# MCB-EMW3166-v2_0_0.net
KiCad netlist of a schematic drawn in EAGLE
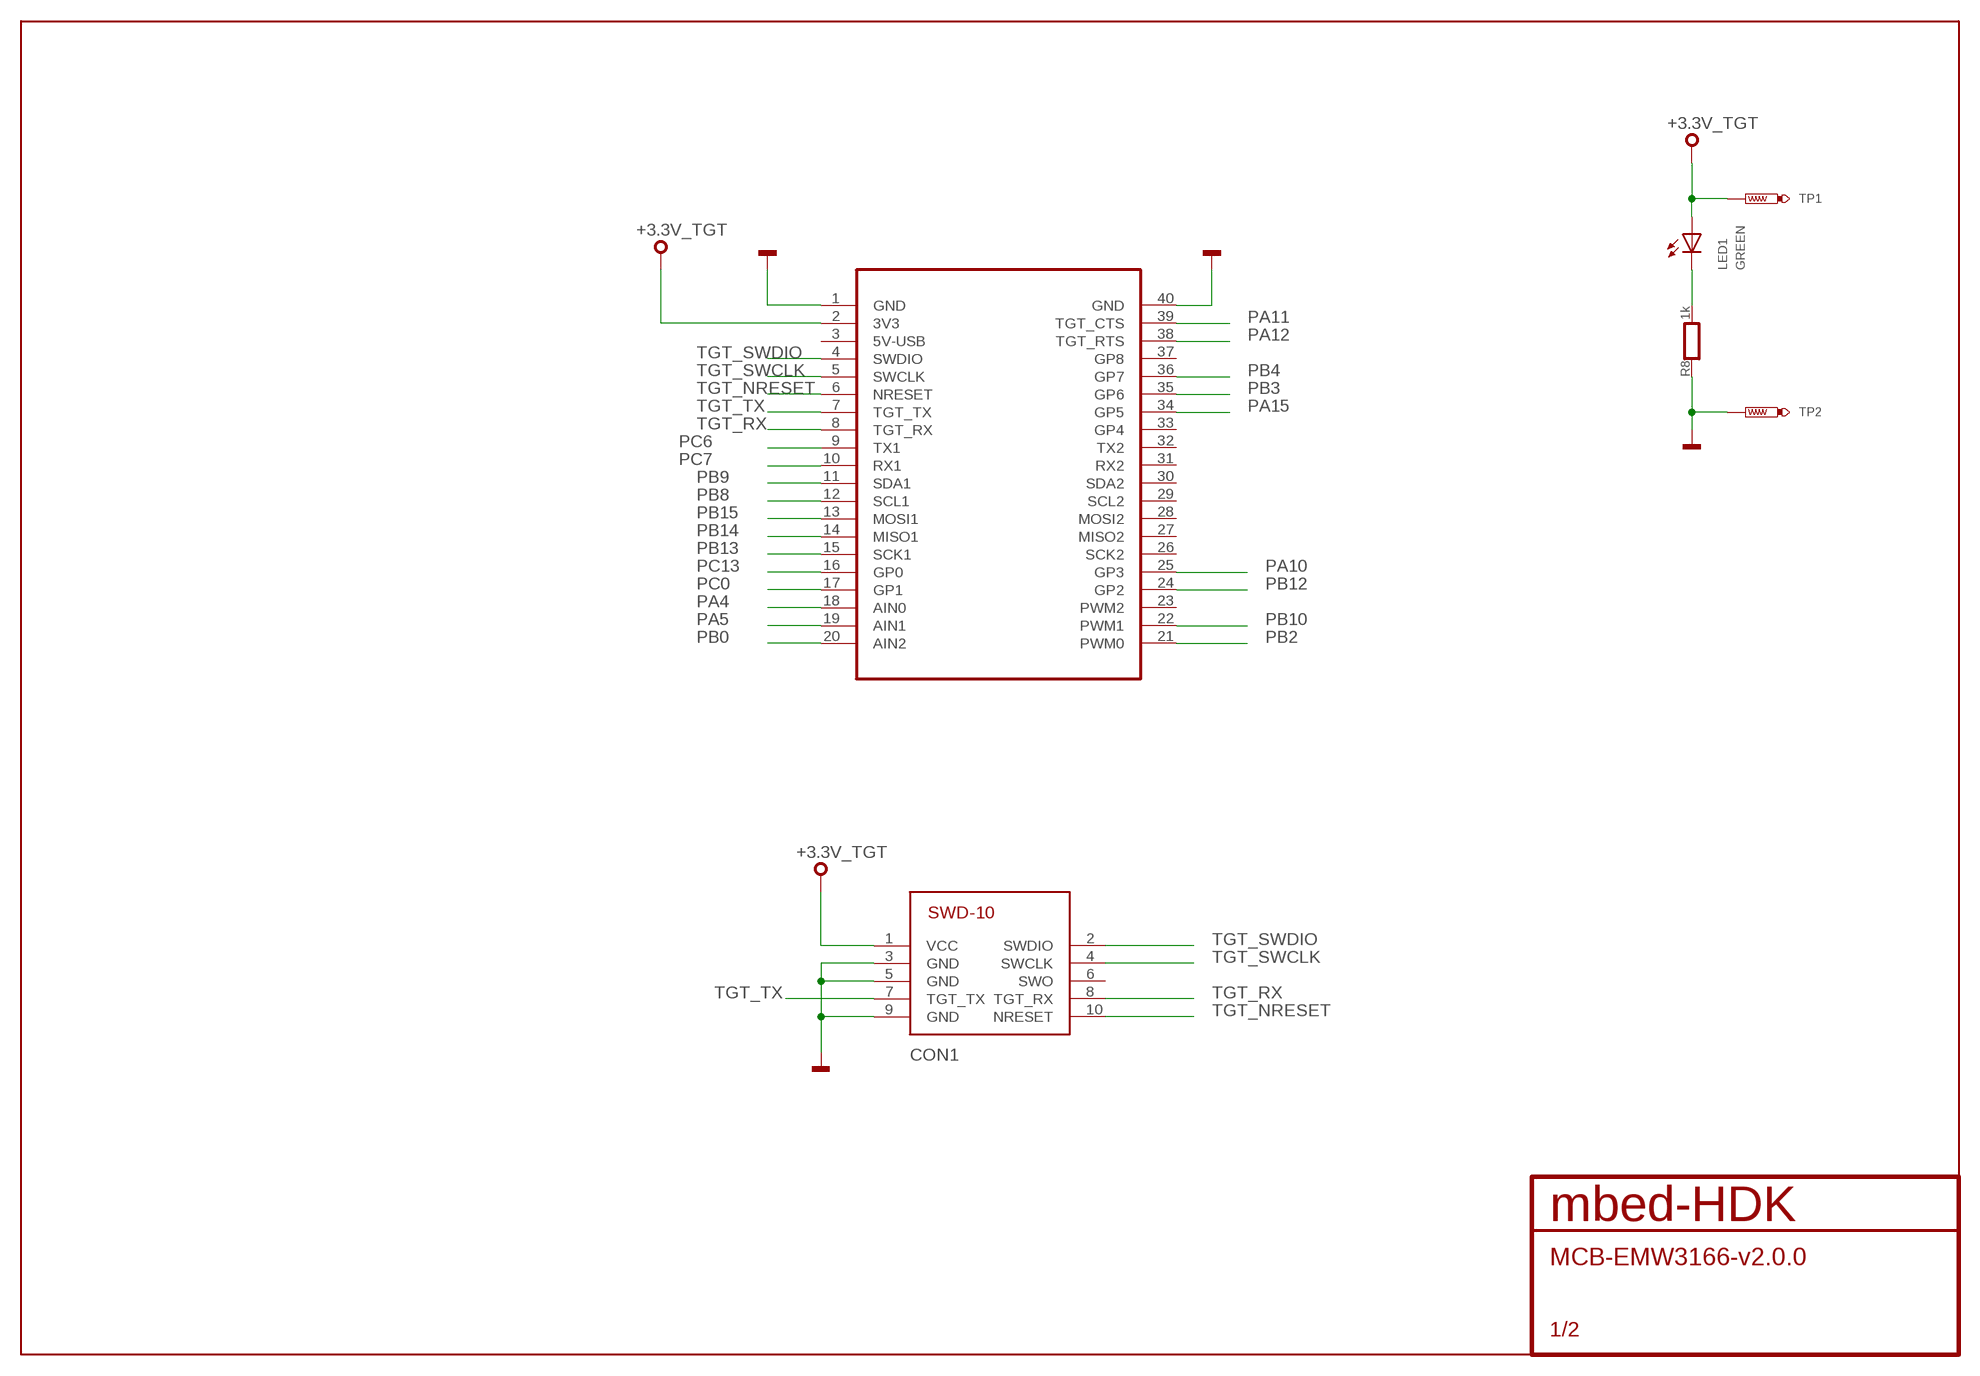
[diagram p0: schematic, sheet 1]
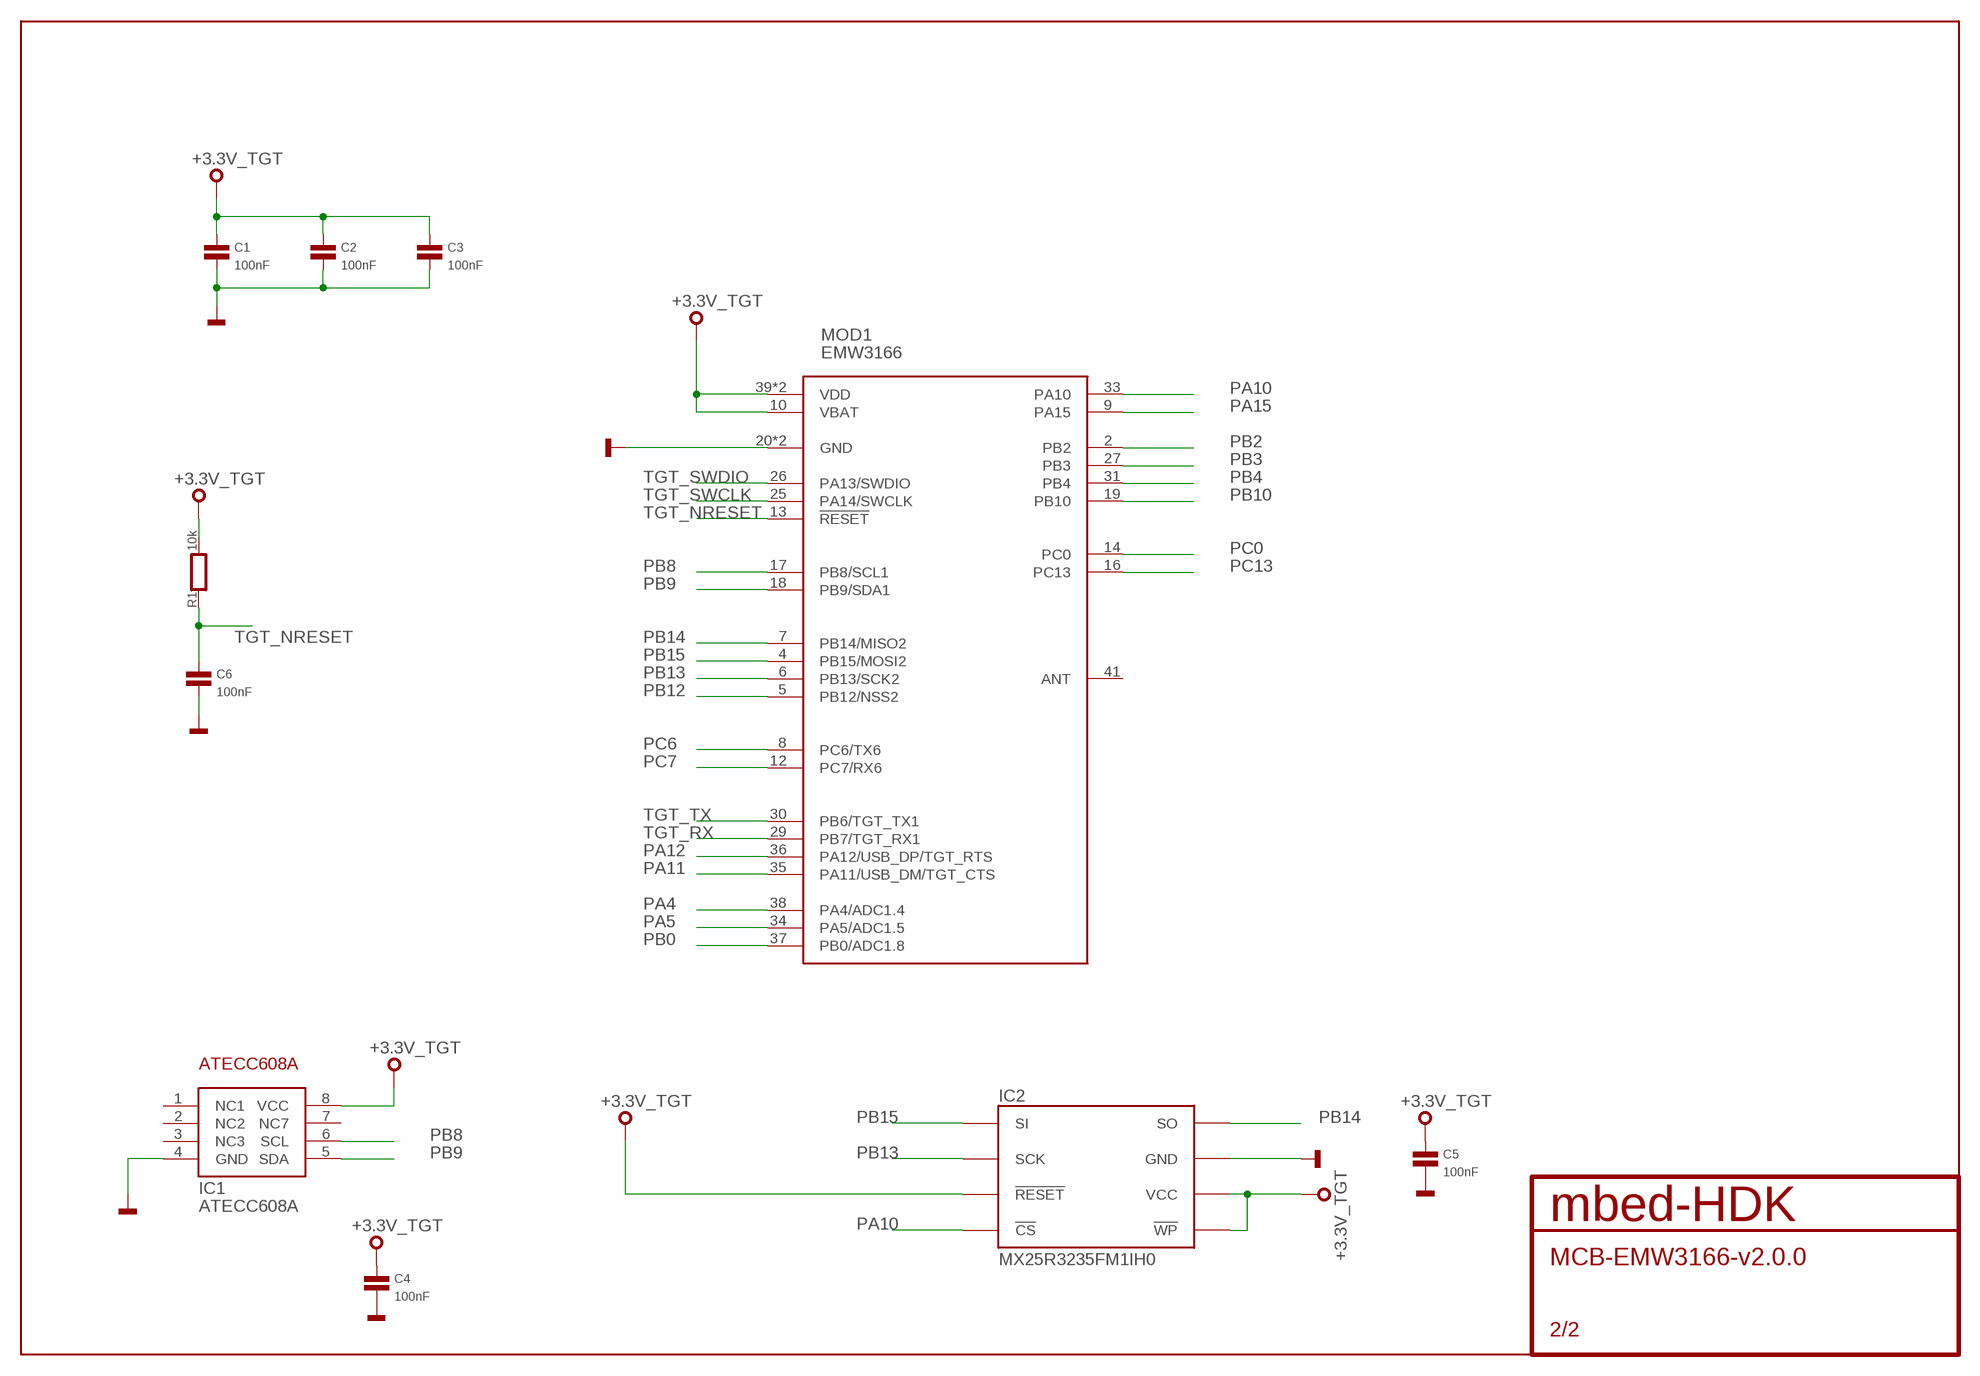
[diagram p1: schematic, sheet 2]

(export (version "E")
  (design (tool "Eeschema 10.0.6"))
  (components
    (comp (ref "C1")
      (value "100nF")
      (footprint "eagle-import:0603")
      (libsource (lib "eagle-import") (part "CAPACITOR0603"))
    )
    (comp (ref "C2")
      (value "100nF")
      (footprint "eagle-import:0603")
      (libsource (lib "eagle-import") (part "CAPACITOR0603"))
    )
    (comp (ref "C3")
      (value "100nF")
      (footprint "eagle-import:0603")
      (libsource (lib "eagle-import") (part "CAPACITOR0603"))
    )
    (comp (ref "C4")
      (value "100nF")
      (footprint "eagle-import:0603")
      (libsource (lib "eagle-import") (part "CAPACITOR0603"))
    )
    (comp (ref "C5")
      (value "100nF")
      (footprint "eagle-import:0603")
      (libsource (lib "eagle-import") (part "CAPACITOR0603"))
    )
    (comp (ref "C6")
      (value "100nF")
      (footprint "eagle-import:0603")
      (libsource (lib "eagle-import") (part "CAPACITOR0603"))
    )
    (comp (ref "IC1")
      (value "ATECC608A")
      (footprint "eagle-import:SO8")
      (libsource (lib "eagle-import") (part "ATECC608A"))
    )
    (comp (ref "IC2")
      (value "MX25R3235FM1IH0")
      (footprint "eagle-import:SO8")
      (fields (field (name "MF") "Macronix"))
      (libsource (lib "eagle-import") (part "MX25R3235FM1IH0"))
    )
    (comp (ref "MOD1")
      (value "EMW3166")
      (footprint "eagle-import:EMW3166")
      (libsource (lib "eagle-import") (part "EMW3166"))
    )
    (comp (ref "R1")
      (value "10k")
      (footprint "eagle-import:0603")
      (libsource (lib "eagle-import") (part "RESISTOR0603"))
    )
    (comp (ref "CON1")
      (value "SWD-10/TC2050_SMD")
      (footprint "eagle-import:FTSH-105-02")
      (libsource (lib "eagle-import") (part "SWD-10/TC2050_SMD"))
    )
    (comp (ref "LED1")
      (value "GREEN")
      (footprint "eagle-import:CHIPLED_0603")
      (fields (field (name "MF") "Wurth Electronics Inc"))
      (libsource (lib "eagle-import") (part "SMD_LED0603"))
    )
    (comp (ref "R8")
      (value "1k")
      (footprint "eagle-import:0603")
      (libsource (lib "eagle-import") (part "RESISTOR0603"))
    )
    (comp (ref "TP1")
      (value "TEST-POINT-50R-PTH")
      (footprint "eagle-import:TP50-PTH")
      (libsource (lib "eagle-import") (part "TEST-POINT-50R-PTH"))
    )
    (comp (ref "TP2")
      (value "TEST-POINT-50R-PTH")
      (footprint "eagle-import:TP50-PTH")
      (libsource (lib "eagle-import") (part "TEST-POINT-50R-PTH"))
    )
    (comp (ref "U$1")
      (value "MODULE_DAUGHTER")
      (footprint "eagle-import:MODULE_DAUGHTER")
      (libsource (lib "eagle-import") (part "MODULE_DAUGHTER"))
    )
  )
  (nets
    (net (code "1") (name "+3.3V_TGT") (class "Default")
      (node (ref "C1") (pin "1") (pinfunction "P$1_1") (pintype "passive"))
      (node (ref "C2") (pin "1") (pinfunction "P$1_1") (pintype "passive"))
      (node (ref "C3") (pin "1") (pinfunction "P$1_1") (pintype "passive"))
      (node (ref "C4") (pin "1") (pinfunction "P$1_1") (pintype "passive"))
      (node (ref "C5") (pin "1") (pinfunction "P$1_1") (pintype "passive"))
      (node (ref "CON1") (pin "1") (pinfunction "VCC_1") (pintype "bidirectional"))
      (node (ref "IC1") (pin "8") (pinfunction "VCC_8") (pintype "bidirectional"))
      (node (ref "IC2") (pin "3") (pinfunction "~{WP}_3") (pintype "bidirectional"))
      (node (ref "IC2") (pin "7") (pinfunction "~{RESET}_7") (pintype "bidirectional"))
      (node (ref "IC2") (pin "8") (pinfunction "VCC_8") (pintype "bidirectional"))
      (node (ref "LED1") (pin "A") (pinfunction "A_A") (pintype "passive"))
      (node (ref "MOD1") (pin "10") (pinfunction "VBAT_10") (pintype "bidirectional"))
      (node (ref "MOD1") (pin "39") (pinfunction "VDD_39") (pintype "bidirectional"))
      (node (ref "MOD1") (pin "40") (pinfunction "VDD_40") (pintype "bidirectional"))
      (node (ref "R1") (pin "2") (pinfunction "P$2_2") (pintype "passive"))
      (node (ref "TP1") (pin "TP") (pinfunction "TP_TP") (pintype "input"))
      (node (ref "U$1") (pin "2") (pinfunction "3V3_2") (pintype "bidirectional"))
    )
    (net (code "2") (name "GND") (class "Default")
      (node (ref "C1") (pin "2") (pinfunction "P$2_2") (pintype "passive"))
      (node (ref "C2") (pin "2") (pinfunction "P$2_2") (pintype "passive"))
      (node (ref "C3") (pin "2") (pinfunction "P$2_2") (pintype "passive"))
      (node (ref "C4") (pin "2") (pinfunction "P$2_2") (pintype "passive"))
      (node (ref "C5") (pin "2") (pinfunction "P$2_2") (pintype "passive"))
      (node (ref "C6") (pin "2") (pinfunction "P$2_2") (pintype "passive"))
      (node (ref "CON1") (pin "3") (pinfunction "GND_3") (pintype "bidirectional"))
      (node (ref "CON1") (pin "5") (pinfunction "GND_5") (pintype "bidirectional"))
      (node (ref "CON1") (pin "9") (pinfunction "GND_9") (pintype "bidirectional"))
      (node (ref "IC1") (pin "4") (pinfunction "GND_4") (pintype "bidirectional"))
      (node (ref "IC2") (pin "4") (pinfunction "GND_4") (pintype "bidirectional"))
      (node (ref "MOD1") (pin "20") (pinfunction "GND_20") (pintype "bidirectional"))
      (node (ref "MOD1") (pin "21") (pinfunction "GND_21") (pintype "bidirectional"))
      (node (ref "R8") (pin "1") (pinfunction "P$1_1") (pintype "passive"))
      (node (ref "TP2") (pin "TP") (pinfunction "TP_TP") (pintype "input"))
      (node (ref "U$1") (pin "1") (pinfunction "GND_1") (pintype "bidirectional"))
      (node (ref "U$1") (pin "40") (pinfunction "GND_40") (pintype "bidirectional"))
    )
    (net (code "3") (name "Net-(R8-P$2)") (class "Default")
      (node (ref "LED1") (pin "C") (pinfunction "C_C") (pintype "passive"))
      (node (ref "R8") (pin "2") (pinfunction "P$2_2") (pintype "passive"))
    )
    (net (code "4") (name "PA4") (class "Default")
      (node (ref "MOD1") (pin "38") (pinfunction "PA4/ADC1.4_38") (pintype "bidirectional"))
      (node (ref "U$1") (pin "18") (pinfunction "AIN0_18") (pintype "bidirectional"))
    )
    (net (code "5") (name "PA5") (class "Default")
      (node (ref "MOD1") (pin "34") (pinfunction "PA5/ADC1.5_34") (pintype "bidirectional"))
      (node (ref "U$1") (pin "19") (pinfunction "AIN1_19") (pintype "bidirectional"))
    )
    (net (code "6") (name "PA10") (class "Default")
      (node (ref "IC2") (pin "1") (pinfunction "~{CS}_1") (pintype "bidirectional"))
      (node (ref "MOD1") (pin "33") (pinfunction "PA10_33") (pintype "bidirectional"))
      (node (ref "U$1") (pin "25") (pinfunction "GP3_25") (pintype "bidirectional"))
    )
    (net (code "7") (name "PA11") (class "Default")
      (node (ref "MOD1") (pin "35") (pinfunction "PA11/USB_DM/TGT_CTS_35") (pintype "bidirectional"))
      (node (ref "U$1") (pin "39") (pinfunction "TGT_CTS_39") (pintype "bidirectional"))
    )
    (net (code "8") (name "PA12") (class "Default")
      (node (ref "MOD1") (pin "36") (pinfunction "PA12/USB_DP/TGT_RTS_36") (pintype "bidirectional"))
      (node (ref "U$1") (pin "38") (pinfunction "TGT_RTS_38") (pintype "bidirectional"))
    )
    (net (code "9") (name "PA15") (class "Default")
      (node (ref "MOD1") (pin "9") (pinfunction "PA15_9") (pintype "bidirectional"))
      (node (ref "U$1") (pin "34") (pinfunction "GP5_34") (pintype "bidirectional"))
    )
    (net (code "10") (name "PB0") (class "Default")
      (node (ref "MOD1") (pin "37") (pinfunction "PB0/ADC1.8_37") (pintype "bidirectional"))
      (node (ref "U$1") (pin "20") (pinfunction "AIN2_20") (pintype "bidirectional"))
    )
    (net (code "11") (name "PB2") (class "Default")
      (node (ref "MOD1") (pin "2") (pinfunction "PB2_2") (pintype "bidirectional"))
      (node (ref "U$1") (pin "21") (pinfunction "PWM0_21") (pintype "bidirectional"))
    )
    (net (code "12") (name "PB3") (class "Default")
      (node (ref "MOD1") (pin "27") (pinfunction "PB3_27") (pintype "bidirectional"))
      (node (ref "U$1") (pin "35") (pinfunction "GP6_35") (pintype "bidirectional"))
    )
    (net (code "13") (name "PB4") (class "Default")
      (node (ref "MOD1") (pin "31") (pinfunction "PB4_31") (pintype "bidirectional"))
      (node (ref "U$1") (pin "36") (pinfunction "GP7_36") (pintype "bidirectional"))
    )
    (net (code "14") (name "PB8") (class "Default")
      (node (ref "IC1") (pin "6") (pinfunction "SCL_6") (pintype "bidirectional"))
      (node (ref "MOD1") (pin "17") (pinfunction "PB8/SCL1_17") (pintype "bidirectional"))
      (node (ref "U$1") (pin "12") (pinfunction "SCL1_12") (pintype "bidirectional"))
    )
    (net (code "15") (name "PB9") (class "Default")
      (node (ref "IC1") (pin "5") (pinfunction "SDA_5") (pintype "bidirectional"))
      (node (ref "MOD1") (pin "18") (pinfunction "PB9/SDA1_18") (pintype "bidirectional"))
      (node (ref "U$1") (pin "11") (pinfunction "SDA1_11") (pintype "bidirectional"))
    )
    (net (code "16") (name "PB10") (class "Default")
      (node (ref "MOD1") (pin "19") (pinfunction "PB10_19") (pintype "bidirectional"))
      (node (ref "U$1") (pin "22") (pinfunction "PWM1_22") (pintype "bidirectional"))
    )
    (net (code "17") (name "PB12") (class "Default")
      (node (ref "MOD1") (pin "5") (pinfunction "PB12/NSS2_5") (pintype "bidirectional"))
      (node (ref "U$1") (pin "24") (pinfunction "GP2_24") (pintype "bidirectional"))
    )
    (net (code "18") (name "PB13") (class "Default")
      (node (ref "IC2") (pin "6") (pinfunction "SCK_6") (pintype "bidirectional"))
      (node (ref "MOD1") (pin "6") (pinfunction "PB13/SCK2_6") (pintype "bidirectional"))
      (node (ref "U$1") (pin "15") (pinfunction "SCK1_15") (pintype "bidirectional"))
    )
    (net (code "19") (name "PB14") (class "Default")
      (node (ref "IC2") (pin "2") (pinfunction "SO_2") (pintype "bidirectional"))
      (node (ref "MOD1") (pin "7") (pinfunction "PB14/MISO2_7") (pintype "bidirectional"))
      (node (ref "U$1") (pin "14") (pinfunction "MISO1_14") (pintype "bidirectional"))
    )
    (net (code "20") (name "PB15") (class "Default")
      (node (ref "IC2") (pin "5") (pinfunction "SI_5") (pintype "bidirectional"))
      (node (ref "MOD1") (pin "4") (pinfunction "PB15/MOSI2_4") (pintype "bidirectional"))
      (node (ref "U$1") (pin "13") (pinfunction "MOSI1_13") (pintype "bidirectional"))
    )
    (net (code "21") (name "PC0") (class "Default")
      (node (ref "MOD1") (pin "14") (pinfunction "PC0_14") (pintype "bidirectional"))
      (node (ref "U$1") (pin "17") (pinfunction "GP1_17") (pintype "bidirectional"))
    )
    (net (code "22") (name "PC6") (class "Default")
      (node (ref "MOD1") (pin "8") (pinfunction "PC6/TX6_8") (pintype "bidirectional"))
      (node (ref "U$1") (pin "9") (pinfunction "TX1_9") (pintype "bidirectional"))
    )
    (net (code "23") (name "PC7") (class "Default")
      (node (ref "MOD1") (pin "12") (pinfunction "PC7/RX6_12") (pintype "bidirectional"))
      (node (ref "U$1") (pin "10") (pinfunction "RX1_10") (pintype "bidirectional"))
    )
    (net (code "24") (name "PC13") (class "Default")
      (node (ref "MOD1") (pin "16") (pinfunction "PC13_16") (pintype "bidirectional"))
      (node (ref "U$1") (pin "16") (pinfunction "GP0_16") (pintype "bidirectional"))
    )
    (net (code "25") (name "TGT_NRESET") (class "Default")
      (node (ref "C6") (pin "1") (pinfunction "P$1_1") (pintype "passive"))
      (node (ref "CON1") (pin "10") (pinfunction "NRESET_10") (pintype "bidirectional"))
      (node (ref "MOD1") (pin "13") (pinfunction "~{RESET}_13") (pintype "bidirectional"))
      (node (ref "R1") (pin "1") (pinfunction "P$1_1") (pintype "passive"))
      (node (ref "U$1") (pin "6") (pinfunction "NRESET_6") (pintype "bidirectional"))
    )
    (net (code "26") (name "TGT_RX") (class "Default")
      (node (ref "CON1") (pin "8") (pinfunction "TGT_RX_8") (pintype "bidirectional"))
      (node (ref "MOD1") (pin "29") (pinfunction "PB7/TGT_RX1_29") (pintype "bidirectional"))
      (node (ref "U$1") (pin "8") (pinfunction "TGT_RX_8") (pintype "bidirectional"))
    )
    (net (code "27") (name "TGT_SWCLK") (class "Default")
      (node (ref "CON1") (pin "4") (pinfunction "SWCLK_4") (pintype "bidirectional"))
      (node (ref "MOD1") (pin "25") (pinfunction "PA14/SWCLK_25") (pintype "bidirectional"))
      (node (ref "U$1") (pin "5") (pinfunction "SWCLK_5") (pintype "bidirectional"))
    )
    (net (code "28") (name "TGT_SWDIO") (class "Default")
      (node (ref "CON1") (pin "2") (pinfunction "SWDIO_2") (pintype "bidirectional"))
      (node (ref "MOD1") (pin "26") (pinfunction "PA13/SWDIO_26") (pintype "bidirectional"))
      (node (ref "U$1") (pin "4") (pinfunction "SWDIO_4") (pintype "bidirectional"))
    )
    (net (code "29") (name "TGT_TX") (class "Default")
      (node (ref "CON1") (pin "7") (pinfunction "TGT_TX_7") (pintype "bidirectional"))
      (node (ref "MOD1") (pin "30") (pinfunction "PB6/TGT_TX1_30") (pintype "bidirectional"))
      (node (ref "U$1") (pin "7") (pinfunction "TGT_TX_7") (pintype "bidirectional"))
    )
    (net (code "30") (name "unconnected-(CON1-SWO-Pad6)") (class "Default")
      (node (ref "CON1") (pin "6") (pinfunction "SWO_6") (pintype "bidirectional"))
    )
    (net (code "31") (name "unconnected-(IC1-NC1-Pad1)") (class "Default")
      (node (ref "IC1") (pin "1") (pinfunction "NC1_1") (pintype "bidirectional"))
    )
    (net (code "32") (name "unconnected-(IC1-NC2-Pad2)") (class "Default")
      (node (ref "IC1") (pin "2") (pinfunction "NC2_2") (pintype "bidirectional"))
    )
    (net (code "33") (name "unconnected-(IC1-NC3-Pad3)") (class "Default")
      (node (ref "IC1") (pin "3") (pinfunction "NC3_3") (pintype "bidirectional"))
    )
    (net (code "34") (name "unconnected-(IC1-NC7-Pad7)") (class "Default")
      (node (ref "IC1") (pin "7") (pinfunction "NC7_7") (pintype "bidirectional"))
    )
    (net (code "35") (name "unconnected-(MOD1-ANT-Pad41)") (class "Default")
      (node (ref "MOD1") (pin "41") (pinfunction "ANT_41") (pintype "bidirectional"))
    )
    (net (code "36") (name "unconnected-(U$1-5V-USB-Pad3)") (class "Default")
      (node (ref "U$1") (pin "3") (pinfunction "5V-USB_3") (pintype "bidirectional"))
    )
    (net (code "37") (name "unconnected-(U$1-GP4-Pad33)") (class "Default")
      (node (ref "U$1") (pin "33") (pinfunction "GP4_33") (pintype "bidirectional"))
    )
    (net (code "38") (name "unconnected-(U$1-GP8-Pad37)") (class "Default")
      (node (ref "U$1") (pin "37") (pinfunction "GP8_37") (pintype "bidirectional"))
    )
    (net (code "39") (name "unconnected-(U$1-MISO2-Pad27)") (class "Default")
      (node (ref "U$1") (pin "27") (pinfunction "MISO2_27") (pintype "bidirectional"))
    )
    (net (code "40") (name "unconnected-(U$1-MOSI2-Pad28)") (class "Default")
      (node (ref "U$1") (pin "28") (pinfunction "MOSI2_28") (pintype "bidirectional"))
    )
    (net (code "41") (name "unconnected-(U$1-PWM2-Pad23)") (class "Default")
      (node (ref "U$1") (pin "23") (pinfunction "PWM2_23") (pintype "bidirectional"))
    )
    (net (code "42") (name "unconnected-(U$1-RX2-Pad31)") (class "Default")
      (node (ref "U$1") (pin "31") (pinfunction "RX2_31") (pintype "bidirectional"))
    )
    (net (code "43") (name "unconnected-(U$1-SCK2-Pad26)") (class "Default")
      (node (ref "U$1") (pin "26") (pinfunction "SCK2_26") (pintype "bidirectional"))
    )
    (net (code "44") (name "unconnected-(U$1-SCL2-Pad29)") (class "Default")
      (node (ref "U$1") (pin "29") (pinfunction "SCL2_29") (pintype "bidirectional"))
    )
    (net (code "45") (name "unconnected-(U$1-SDA2-Pad30)") (class "Default")
      (node (ref "U$1") (pin "30") (pinfunction "SDA2_30") (pintype "bidirectional"))
    )
    (net (code "46") (name "unconnected-(U$1-TX2-Pad32)") (class "Default")
      (node (ref "U$1") (pin "32") (pinfunction "TX2_32") (pintype "bidirectional"))
    )
  )
)
